# Controller.net
KiCad netlist of a schematic drawn in Altium Designer
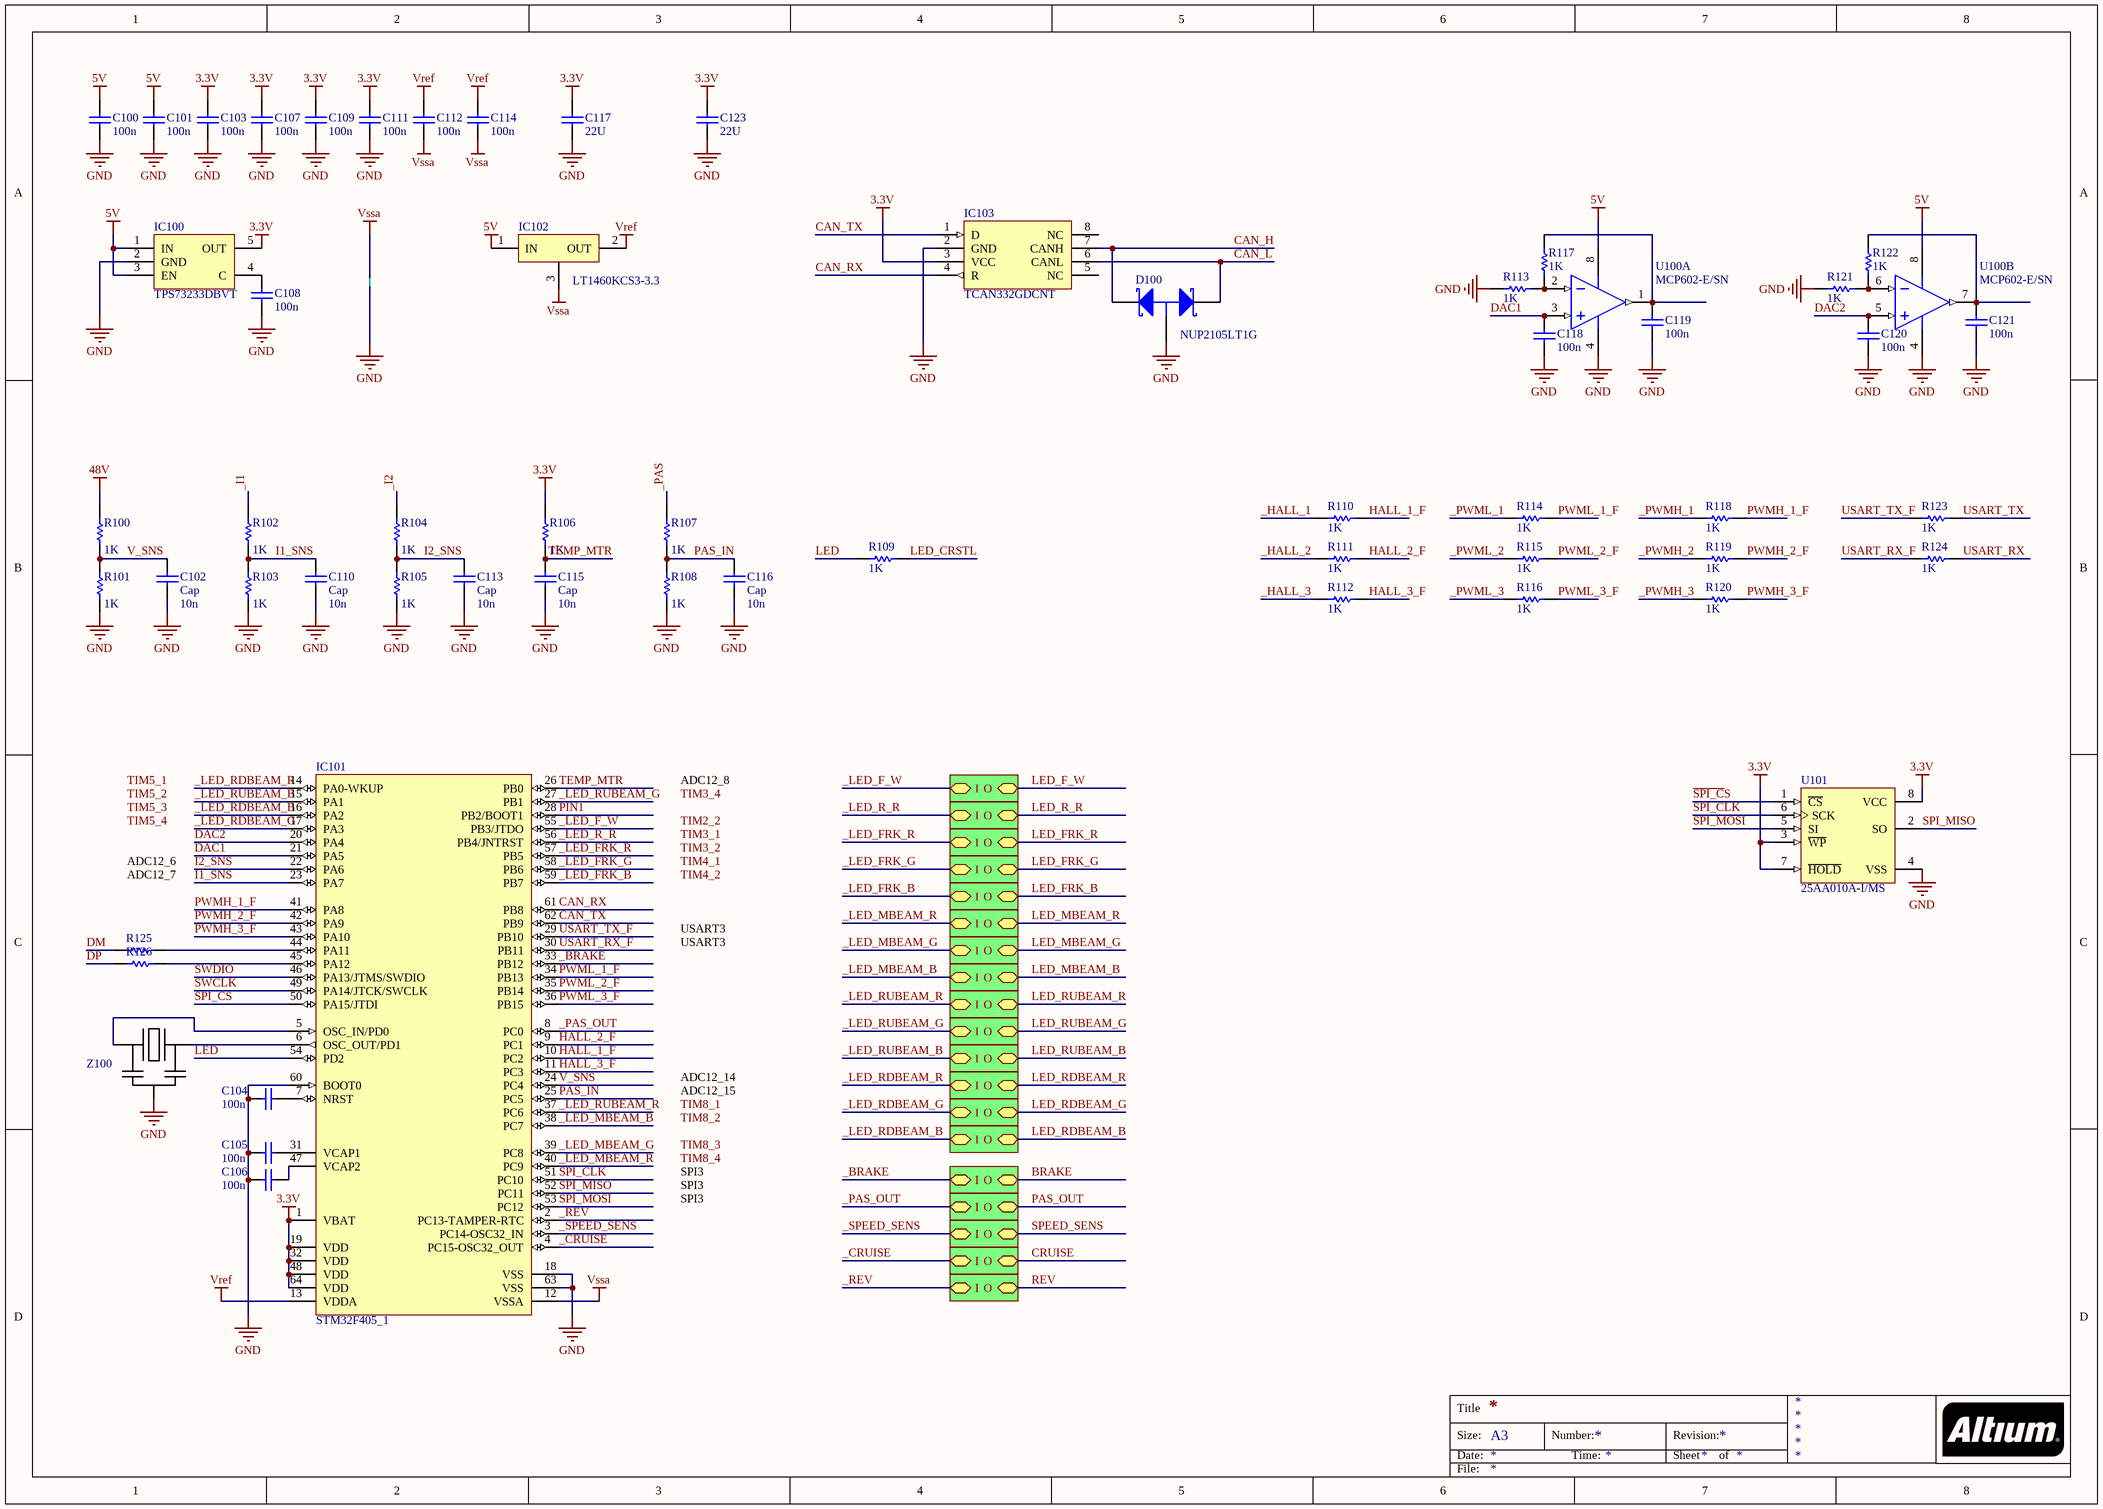
[diagram p0: Controller.SchDoc]

(export (version "E")
  (design (tool "Eeschema 10.0.6"))
  (components
    (comp (ref "C100")
      (value "100n")
      (footprint "0603x")
      (description "Capacitor")
      (fields (field (name "Comment") "Cap") (field (name "PUBLISHER") "Altium Limited"))
      (libsource (lib "Miscellaneous Devices") (part "Cap"))
    )
    (comp (ref "C101")
      (value "100n")
      (footprint "0603x")
      (description "Capacitor")
      (fields (field (name "Comment") "Cap") (field (name "PUBLISHER") "Altium Limited"))
      (libsource (lib "Miscellaneous Devices") (part "Cap"))
    )
    (comp (ref "C102")
      (value "Cap")
      (footprint "0603x")
      (description "Capacitor")
      (fields (field (name "ALTIUM_VALUE") "10n") (field (name "PUBLISHER") "Altium Limited"))
      (libsource (lib "Miscellaneous Devices") (part "Cap"))
    )
    (comp (ref "C103")
      (value "100n")
      (footprint "0603x")
      (description "Capacitor")
      (fields (field (name "Comment") "Cap") (field (name "PUBLISHER") "Altium Limited"))
      (libsource (lib "Miscellaneous Devices") (part "Cap"))
    )
    (comp (ref "C104")
      (value "100n")
      (footprint "0402x")
      (description "Capacitor")
      (fields (field (name "Comment") "Cap") (field (name "PUBLISHER") "Altium Limited"))
      (libsource (lib "Miscellaneous Devices") (part "Cap"))
    )
    (comp (ref "C105")
      (value "100n")
      (footprint "0603x")
      (description "Capacitor")
      (fields (field (name "Comment") "Cap") (field (name "PUBLISHER") "Altium Limited"))
      (libsource (lib "Miscellaneous Devices") (part "Cap"))
    )
    (comp (ref "C106")
      (value "100n")
      (footprint "0603x")
      (description "Capacitor")
      (fields (field (name "Comment") "Cap") (field (name "PUBLISHER") "Altium Limited"))
      (libsource (lib "Miscellaneous Devices") (part "Cap"))
    )
    (comp (ref "C107")
      (value "100n")
      (footprint "0603x")
      (description "Capacitor")
      (fields (field (name "Comment") "Cap") (field (name "PUBLISHER") "Altium Limited"))
      (libsource (lib "Miscellaneous Devices") (part "Cap"))
    )
    (comp (ref "C108")
      (value "100n")
      (footprint "0603x")
      (description "Capacitor")
      (fields (field (name "Comment") "Cap") (field (name "PUBLISHER") "Altium Limited"))
      (libsource (lib "Miscellaneous Devices") (part "Cap"))
    )
    (comp (ref "C109")
      (value "100n")
      (footprint "0603x")
      (description "Capacitor")
      (fields (field (name "Comment") "Cap") (field (name "PUBLISHER") "Altium Limited"))
      (libsource (lib "Miscellaneous Devices") (part "Cap"))
    )
    (comp (ref "C110")
      (value "Cap")
      (footprint "0603x")
      (description "Capacitor")
      (fields (field (name "ALTIUM_VALUE") "10n") (field (name "PUBLISHER") "Altium Limited"))
      (libsource (lib "Miscellaneous Devices") (part "Cap"))
    )
    (comp (ref "C111")
      (value "100n")
      (footprint "0603x")
      (description "Capacitor")
      (fields (field (name "Comment") "Cap") (field (name "PUBLISHER") "Altium Limited"))
      (libsource (lib "Miscellaneous Devices") (part "Cap"))
    )
    (comp (ref "C112")
      (value "100n")
      (footprint "0603x")
      (description "Capacitor")
      (fields (field (name "Comment") "Cap") (field (name "PUBLISHER") "Altium Limited"))
      (libsource (lib "Miscellaneous Devices") (part "Cap"))
    )
    (comp (ref "C113")
      (value "Cap")
      (footprint "0603x")
      (description "Capacitor")
      (fields (field (name "ALTIUM_VALUE") "10n") (field (name "PUBLISHER") "Altium Limited"))
      (libsource (lib "Miscellaneous Devices") (part "Cap"))
    )
    (comp (ref "C114")
      (value "100n")
      (footprint "0603x")
      (description "Capacitor")
      (fields (field (name "Comment") "Cap") (field (name "PUBLISHER") "Altium Limited"))
      (libsource (lib "Miscellaneous Devices") (part "Cap"))
    )
    (comp (ref "C115")
      (value "Cap")
      (footprint "0402x")
      (description "Capacitor")
      (fields (field (name "ALTIUM_VALUE") "10n") (field (name "PUBLISHER") "Altium Limited"))
      (libsource (lib "Miscellaneous Devices") (part "Cap"))
    )
    (comp (ref "C116")
      (value "Cap")
      (footprint "0603x")
      (description "Capacitor")
      (fields (field (name "ALTIUM_VALUE") "10n") (field (name "PUBLISHER") "Altium Limited"))
      (libsource (lib "Miscellaneous Devices") (part "Cap"))
    )
    (comp (ref "C117")
      (value "22U")
      (footprint "RR_B")
      (description "Capacitor")
      (fields (field (name "Comment") "Cap") (field (name "PUBLISHER") "Altium Limited"))
      (libsource (lib "Miscellaneous Devices") (part "Cap"))
    )
    (comp (ref "C118")
      (value "100n")
      (footprint "0603x")
      (description "Capacitor")
      (fields (field (name "Comment") "Cap") (field (name "PUBLISHER") "Altium Limited"))
      (libsource (lib "Miscellaneous Devices") (part "Cap"))
    )
    (comp (ref "C119")
      (value "100n")
      (footprint "0603x")
      (description "Capacitor")
      (fields (field (name "Comment") "Cap") (field (name "PUBLISHER") "Altium Limited"))
      (libsource (lib "Miscellaneous Devices") (part "Cap"))
    )
    (comp (ref "C120")
      (value "100n")
      (footprint "0603x")
      (description "Capacitor")
      (fields (field (name "Comment") "Cap") (field (name "PUBLISHER") "Altium Limited"))
      (libsource (lib "Miscellaneous Devices") (part "Cap"))
    )
    (comp (ref "C121")
      (value "100n")
      (footprint "0603x")
      (description "Capacitor")
      (fields (field (name "Comment") "Cap") (field (name "PUBLISHER") "Altium Limited"))
      (libsource (lib "Miscellaneous Devices") (part "Cap"))
    )
    (comp (ref "C123")
      (value "22U")
      (footprint "RR_B")
      (description "Capacitor")
      (fields (field (name "Comment") "Cap") (field (name "PUBLISHER") "Altium Limited"))
      (libsource (lib "Miscellaneous Devices") (part "Cap"))
    )
    (comp (ref "D100")
      (value "NUP2105LT1G")
      (footprint "SOT23_M")
      (description "Schottky Barrier Double Diode")
      (libsource (lib "EDDLib") (part "BAT54A"))
    )
    (comp (ref "IC100")
      (value "TPS73233DBVT")
      (footprint "SOT23-5_L")
      (libsource (lib "EDDLib") (part "TPS7xx33"))
    )
    (comp (ref "IC101")
      (value "STM32F405_1")
      (footprint "LQFP64_L")
      (description "STM32 ARM-based 32-bit MCU")
      (libsource (lib "EDDLib") (part "STM32F405_1"))
    )
    (comp (ref "IC102")
      (value "LT1460KCS3-3.3")
      (footprint "SOT-23")
      (libsource (lib "EDDLib") (part "PreciseRef"))
    )
    (comp (ref "IC103")
      (value "TCAN332GDCNT")
      (footprint "SOT23-8_L")
      (libsource (lib "EDDLib") (part "TCAN332GDCNT"))
    )
    (comp (ref "NT100")
      (value "NET_TIE")
      (footprint "NET_TIE_20mil")
      (description "Net tie")
      (libsource (lib "CustomLib") (part "Net tie"))
    )
    (comp (ref "R100")
      (value "1K")
      (footprint "0603x")
      (description "Resistor")
      (fields (field (name "Comment") "Res1") (field (name "PUBLISHER") "Altium Limited"))
      (libsource (lib "Miscellaneous Devices") (part "Res1"))
    )
    (comp (ref "R101")
      (value "1K")
      (footprint "0603x")
      (description "Resistor")
      (fields (field (name "Comment") "Res1") (field (name "PUBLISHER") "Altium Limited"))
      (libsource (lib "Miscellaneous Devices") (part "Res1"))
    )
    (comp (ref "R102")
      (value "1K")
      (footprint "0603x")
      (description "Resistor")
      (fields (field (name "Comment") "Res1") (field (name "PUBLISHER") "Altium Limited"))
      (libsource (lib "Miscellaneous Devices") (part "Res1"))
    )
    (comp (ref "R103")
      (value "1K")
      (footprint "0603x")
      (description "Resistor")
      (fields (field (name "Comment") "Res1") (field (name "PUBLISHER") "Altium Limited"))
      (libsource (lib "Miscellaneous Devices") (part "Res1"))
    )
    (comp (ref "R104")
      (value "1K")
      (footprint "0603x")
      (description "Resistor")
      (fields (field (name "Comment") "Res1") (field (name "PUBLISHER") "Altium Limited"))
      (libsource (lib "Miscellaneous Devices") (part "Res1"))
    )
    (comp (ref "R105")
      (value "1K")
      (footprint "0603x")
      (description "Resistor")
      (fields (field (name "Comment") "Res1") (field (name "PUBLISHER") "Altium Limited"))
      (libsource (lib "Miscellaneous Devices") (part "Res1"))
    )
    (comp (ref "R106")
      (value "1K")
      (footprint "0603x")
      (description "Resistor")
      (fields (field (name "Comment") "Res1") (field (name "PUBLISHER") "Altium Limited"))
      (libsource (lib "Miscellaneous Devices") (part "Res1"))
    )
    (comp (ref "R107")
      (value "1K")
      (footprint "0603x")
      (description "Resistor")
      (fields (field (name "Comment") "Res1") (field (name "PUBLISHER") "Altium Limited"))
      (libsource (lib "Miscellaneous Devices") (part "Res1"))
    )
    (comp (ref "R108")
      (value "1K")
      (footprint "0603x")
      (description "Resistor")
      (fields (field (name "Comment") "Res1") (field (name "PUBLISHER") "Altium Limited"))
      (libsource (lib "Miscellaneous Devices") (part "Res1"))
    )
    (comp (ref "R109")
      (value "1K")
      (footprint "0603x")
      (description "Resistor")
      (fields (field (name "Comment") "Res1") (field (name "PUBLISHER") "Altium Limited"))
      (libsource (lib "Miscellaneous Devices") (part "Res1"))
    )
    (comp (ref "R110")
      (value "1K")
      (footprint "0603x")
      (description "Resistor")
      (fields (field (name "Comment") "Res1") (field (name "PUBLISHER") "Altium Limited"))
      (libsource (lib "Miscellaneous Devices") (part "Res1"))
    )
    (comp (ref "R111")
      (value "1K")
      (footprint "0603x")
      (description "Resistor")
      (fields (field (name "Comment") "Res1") (field (name "PUBLISHER") "Altium Limited"))
      (libsource (lib "Miscellaneous Devices") (part "Res1"))
    )
    (comp (ref "R112")
      (value "1K")
      (footprint "0603x")
      (description "Resistor")
      (fields (field (name "Comment") "Res1") (field (name "PUBLISHER") "Altium Limited"))
      (libsource (lib "Miscellaneous Devices") (part "Res1"))
    )
    (comp (ref "R113")
      (value "1K")
      (footprint "0603x")
      (description "Resistor")
      (fields (field (name "Comment") "Res1") (field (name "PUBLISHER") "Altium Limited"))
      (libsource (lib "Miscellaneous Devices") (part "Res1"))
    )
    (comp (ref "R114")
      (value "1K")
      (footprint "0603x")
      (description "Resistor")
      (fields (field (name "Comment") "Res1") (field (name "PUBLISHER") "Altium Limited"))
      (libsource (lib "Miscellaneous Devices") (part "Res1"))
    )
    (comp (ref "R115")
      (value "1K")
      (footprint "0603x")
      (description "Resistor")
      (fields (field (name "Comment") "Res1") (field (name "PUBLISHER") "Altium Limited"))
      (libsource (lib "Miscellaneous Devices") (part "Res1"))
    )
    (comp (ref "R116")
      (value "1K")
      (footprint "0603x")
      (description "Resistor")
      (fields (field (name "Comment") "Res1") (field (name "PUBLISHER") "Altium Limited"))
      (libsource (lib "Miscellaneous Devices") (part "Res1"))
    )
    (comp (ref "R117")
      (value "1K")
      (footprint "0603x")
      (description "Resistor")
      (fields (field (name "Comment") "Res1") (field (name "PUBLISHER") "Altium Limited"))
      (libsource (lib "Miscellaneous Devices") (part "Res1"))
    )
    (comp (ref "R118")
      (value "1K")
      (footprint "0603x")
      (description "Resistor")
      (fields (field (name "Comment") "Res1") (field (name "PUBLISHER") "Altium Limited"))
      (libsource (lib "Miscellaneous Devices") (part "Res1"))
    )
    (comp (ref "R119")
      (value "1K")
      (footprint "0603x")
      (description "Resistor")
      (fields (field (name "Comment") "Res1") (field (name "PUBLISHER") "Altium Limited"))
      (libsource (lib "Miscellaneous Devices") (part "Res1"))
    )
    (comp (ref "R120")
      (value "1K")
      (footprint "0603x")
      (description "Resistor")
      (fields (field (name "Comment") "Res1") (field (name "PUBLISHER") "Altium Limited"))
      (libsource (lib "Miscellaneous Devices") (part "Res1"))
    )
    (comp (ref "R121")
      (value "1K")
      (footprint "0603x")
      (description "Resistor")
      (fields (field (name "Comment") "Res1") (field (name "PUBLISHER") "Altium Limited"))
      (libsource (lib "Miscellaneous Devices") (part "Res1"))
    )
    (comp (ref "R122")
      (value "1K")
      (footprint "0603x")
      (description "Resistor")
      (fields (field (name "Comment") "Res1") (field (name "PUBLISHER") "Altium Limited"))
      (libsource (lib "Miscellaneous Devices") (part "Res1"))
    )
    (comp (ref "R123")
      (value "1K")
      (footprint "0603x")
      (description "Resistor")
      (fields (field (name "Comment") "Res1") (field (name "PUBLISHER") "Altium Limited"))
      (libsource (lib "Miscellaneous Devices") (part "Res1"))
    )
    (comp (ref "R124")
      (value "1K")
      (footprint "0603x")
      (description "Resistor")
      (fields (field (name "Comment") "Res1") (field (name "PUBLISHER") "Altium Limited"))
      (libsource (lib "Miscellaneous Devices") (part "Res1"))
    )
    (comp (ref "R125")
      (value "Res1")
      (footprint "0603x")
      (description "Resistor")
      (fields (field (name "PUBLISHER") "Altium Limited"))
      (libsource (lib "Miscellaneous Devices") (part "Res1"))
    )
    (comp (ref "R126")
      (value "Res1")
      (footprint "0603x")
      (description "Resistor")
      (fields (field (name "PUBLISHER") "Altium Limited"))
      (libsource (lib "Miscellaneous Devices") (part "Res1"))
    )
    (comp (ref "U100")
      (value "MCP602-E/SN")
      (footprint "SOIC-SN8_N")
      (description "2.7V to 6.0V Single Supply CMOS Operational Amplifier, 8-Pin SOIC, Extended Temperature")
      (fields (field (name "PUBLISHER") "Altium Limited"))
      (libsource (lib "Microchip Linear Devices") (part "MCP602-E/SN"))
    )
    (comp (ref "U101")
      (value "25AA010A-I/MS")
      (footprint "SO-8_N")
      (description "1K SPI Bus Serial EEPROM, 8-Pin MSOP, Industrial Temperature")
      (fields (field (name "PUBLISHER") "Altium Limited"))
      (libsource (lib "Microchip Memory SPI Serial EEPROM") (part "25AA010A-I/MS"))
    )
    (comp (ref "Z100")
      (value "AWSCR-8.00CV-T")
      (footprint "CRYSTAL_3.2X1.3")
      (libsource (lib "EDDLib") (part "Crystal_smd_with_caps"))
    )
  )
  (nets
    (net (code "2") (name "/CAN_H") (class "Default")
      (node (ref "D100") (pin "2") (pinfunction "K2_2") (pintype "passive"))
      (node (ref "IC103") (pin "7") (pinfunction "CANH_7") (pintype "passive"))
    )
    (net (code "3") (name "/CAN_L") (class "Default")
      (node (ref "D100") (pin "3") (pinfunction "K1_3") (pintype "passive"))
      (node (ref "IC103") (pin "6") (pinfunction "CANL_6") (pintype "passive"))
    )
    (net (code "4") (name "/CAN_RX") (class "Default")
      (node (ref "IC101") (pin "61") (pinfunction "PB8_61") (pintype "bidirectional"))
      (node (ref "IC103") (pin "4") (pinfunction "R_4") (pintype "output"))
    )
    (net (code "5") (name "/CAN_TX") (class "Default")
      (node (ref "IC101") (pin "62") (pinfunction "PB9_62") (pintype "bidirectional"))
      (node (ref "IC103") (pin "1") (pinfunction "D_1") (pintype "input"))
    )
    (net (code "7") (name "/DAC1") (class "Default")
      (node (ref "C118") (pin "1") (pinfunction "1_1") (pintype "passive"))
      (node (ref "IC101") (pin "21") (pinfunction "PA5_21") (pintype "bidirectional"))
      (node (ref "U100") (pin "3") (pinfunction "VINA+_3") (pintype "input"))
    )
    (net (code "8") (name "/DAC2") (class "Default")
      (node (ref "C120") (pin "1") (pinfunction "1_1") (pintype "passive"))
      (node (ref "IC101") (pin "20") (pinfunction "PA4_20") (pintype "bidirectional"))
      (node (ref "U100") (pin "5") (pinfunction "VINB+_5") (pintype "input"))
    )
    (net (code "9") (name "/DM") (class "Default")
      (node (ref "R125") (pin "1") (pinfunction "1_1") (pintype "passive"))
    )
    (net (code "10") (name "/DP") (class "Default")
      (node (ref "R126") (pin "1") (pinfunction "1_1") (pintype "passive"))
    )
    (net (code "11") (name "/HALL_1_F") (class "Default")
      (node (ref "IC101") (pin "10") (pinfunction "PC2_10") (pintype "bidirectional"))
      (node (ref "R110") (pin "2") (pinfunction "2_2") (pintype "passive"))
    )
    (net (code "12") (name "/HALL_2_F") (class "Default")
      (node (ref "IC101") (pin "9") (pinfunction "PC1_9") (pintype "bidirectional"))
      (node (ref "R111") (pin "2") (pinfunction "2_2") (pintype "passive"))
    )
    (net (code "13") (name "/HALL_3_F") (class "Default")
      (node (ref "IC101") (pin "11") (pinfunction "PC3_11") (pintype "bidirectional"))
      (node (ref "R112") (pin "2") (pinfunction "2_2") (pintype "passive"))
    )
    (net (code "14") (name "/I1_SNS") (class "Default")
      (node (ref "C110") (pin "1") (pinfunction "1_1") (pintype "passive"))
      (node (ref "IC101") (pin "23") (pinfunction "PA7_23") (pintype "bidirectional"))
      (node (ref "R102") (pin "2") (pinfunction "2_2") (pintype "passive"))
      (node (ref "R103") (pin "1") (pinfunction "1_1") (pintype "passive"))
    )
    (net (code "15") (name "/I2_SNS") (class "Default")
      (node (ref "C113") (pin "1") (pinfunction "1_1") (pintype "passive"))
      (node (ref "IC101") (pin "22") (pinfunction "PA6_22") (pintype "bidirectional"))
      (node (ref "R104") (pin "2") (pinfunction "2_2") (pintype "passive"))
      (node (ref "R105") (pin "1") (pinfunction "1_1") (pintype "passive"))
    )
    (net (code "16") (name "/LED") (class "Default")
      (node (ref "IC101") (pin "54") (pinfunction "PD2_54") (pintype "bidirectional"))
      (node (ref "R109") (pin "1") (pinfunction "1_1") (pintype "passive"))
    )
    (net (code "17") (name "/LED_CRSTL") (class "Default")
      (node (ref "R109") (pin "2") (pinfunction "2_2") (pintype "passive"))
    )
    (net (code "32") (name "/PAS_IN") (class "Default")
      (node (ref "C116") (pin "1") (pinfunction "1_1") (pintype "passive"))
      (node (ref "IC101") (pin "25") (pinfunction "PC5_25") (pintype "bidirectional"))
      (node (ref "R107") (pin "2") (pinfunction "2_2") (pintype "passive"))
      (node (ref "R108") (pin "1") (pinfunction "1_1") (pintype "passive"))
    )
    (net (code "34") (name "/PIN1") (class "Default")
      (node (ref "IC101") (pin "28") (pinfunction "PB2/BOOT1_28") (pintype "bidirectional"))
    )
    (net (code "35") (name "/PWMH_1_F") (class "Default")
      (node (ref "IC101") (pin "41") (pinfunction "PA8_41") (pintype "bidirectional"))
      (node (ref "R118") (pin "2") (pinfunction "2_2") (pintype "passive"))
    )
    (net (code "36") (name "/PWMH_2_F") (class "Default")
      (node (ref "IC101") (pin "42") (pinfunction "PA9_42") (pintype "bidirectional"))
      (node (ref "R119") (pin "2") (pinfunction "2_2") (pintype "passive"))
    )
    (net (code "37") (name "/PWMH_3_F") (class "Default")
      (node (ref "IC101") (pin "43") (pinfunction "PA10_43") (pintype "bidirectional"))
      (node (ref "R120") (pin "2") (pinfunction "2_2") (pintype "passive"))
    )
    (net (code "38") (name "/PWML_1_F") (class "Default")
      (node (ref "IC101") (pin "34") (pinfunction "PB13_34") (pintype "bidirectional"))
      (node (ref "R114") (pin "2") (pinfunction "2_2") (pintype "passive"))
    )
    (net (code "39") (name "/PWML_2_F") (class "Default")
      (node (ref "IC101") (pin "35") (pinfunction "PB14_35") (pintype "bidirectional"))
      (node (ref "R115") (pin "2") (pinfunction "2_2") (pintype "passive"))
    )
    (net (code "40") (name "/PWML_3_F") (class "Default")
      (node (ref "IC101") (pin "36") (pinfunction "PB15_36") (pintype "bidirectional"))
      (node (ref "R116") (pin "2") (pinfunction "2_2") (pintype "passive"))
    )
    (net (code "43") (name "/SPI_CLK") (class "Default")
      (node (ref "IC101") (pin "51") (pinfunction "PC10_51") (pintype "bidirectional"))
      (node (ref "U101") (pin "6") (pinfunction "SCK_6") (pintype "input"))
    )
    (net (code "44") (name "/SPI_MISO") (class "Default")
      (node (ref "IC101") (pin "52") (pinfunction "PC11_52") (pintype "bidirectional"))
      (node (ref "U101") (pin "2") (pinfunction "SO_2") (pintype "tri_state"))
    )
    (net (code "45") (name "/SPI_MOSI") (class "Default")
      (node (ref "IC101") (pin "53") (pinfunction "PC12_53") (pintype "bidirectional"))
      (node (ref "U101") (pin "5") (pinfunction "SI_5") (pintype "input"))
    )
    (net (code "46") (name "/SWCLK") (class "Default")
      (node (ref "IC101") (pin "49") (pinfunction "PA14/JTCK/SWCLK_49") (pintype "bidirectional"))
    )
    (net (code "47") (name "/SWDIO") (class "Default")
      (node (ref "IC101") (pin "46") (pinfunction "PA13/JTMS/SWDIO_46") (pintype "bidirectional"))
    )
    (net (code "48") (name "/TEMP_MTR") (class "Default")
      (node (ref "C115") (pin "1") (pinfunction "1_1") (pintype "passive"))
      (node (ref "IC101") (pin "26") (pinfunction "PB0_26") (pintype "bidirectional"))
      (node (ref "R106") (pin "2") (pinfunction "2_2") (pintype "passive"))
    )
    (net (code "63") (name "/USART_RX") (class "Default")
      (node (ref "R124") (pin "2") (pinfunction "2_2") (pintype "passive"))
    )
    (net (code "64") (name "/USART_RX_F") (class "Default")
      (node (ref "IC101") (pin "30") (pinfunction "PB11_30") (pintype "bidirectional"))
      (node (ref "R124") (pin "1") (pinfunction "1_1") (pintype "passive"))
    )
    (net (code "65") (name "/USART_TX") (class "Default")
      (node (ref "R123") (pin "2") (pinfunction "2_2") (pintype "passive"))
    )
    (net (code "66") (name "/USART_TX_F") (class "Default")
      (node (ref "IC101") (pin "29") (pinfunction "PB10_29") (pintype "bidirectional"))
      (node (ref "R123") (pin "1") (pinfunction "1_1") (pintype "passive"))
    )
    (net (code "67") (name "/V_SNS") (class "Default")
      (node (ref "C102") (pin "1") (pinfunction "1_1") (pintype "passive"))
      (node (ref "IC101") (pin "24") (pinfunction "PC4_24") (pintype "bidirectional"))
      (node (ref "R100") (pin "2") (pinfunction "2_2") (pintype "passive"))
      (node (ref "R101") (pin "1") (pinfunction "1_1") (pintype "passive"))
    )
    (net (code "68") (name "/_BRAKE") (class "Default")
      (node (ref "IC101") (pin "33") (pinfunction "PB12_33") (pintype "bidirectional"))
    )
    (net (code "69") (name "/_CRUISE") (class "Default")
      (node (ref "IC101") (pin "4") (pinfunction "PC15-OSC32_OUT_4") (pintype "bidirectional"))
    )
    (net (code "70") (name "/_HALL_1") (class "Default")
      (node (ref "R110") (pin "1") (pinfunction "1_1") (pintype "passive"))
    )
    (net (code "71") (name "/_HALL_2") (class "Default")
      (node (ref "R111") (pin "1") (pinfunction "1_1") (pintype "passive"))
    )
    (net (code "72") (name "/_HALL_3") (class "Default")
      (node (ref "R112") (pin "1") (pinfunction "1_1") (pintype "passive"))
    )
    (net (code "73") (name "/_I1") (class "Default")
      (node (ref "R102") (pin "1") (pinfunction "1_1") (pintype "passive"))
    )
    (net (code "74") (name "/_I2") (class "Default")
      (node (ref "R104") (pin "1") (pinfunction "1_1") (pintype "passive"))
    )
    (net (code "75") (name "/_LED_FRK_B") (class "Default")
      (node (ref "IC101") (pin "59") (pinfunction "PB7_59") (pintype "bidirectional"))
    )
    (net (code "76") (name "/_LED_FRK_G") (class "Default")
      (node (ref "IC101") (pin "58") (pinfunction "PB6_58") (pintype "bidirectional"))
    )
    (net (code "77") (name "/_LED_FRK_R") (class "Default")
      (node (ref "IC101") (pin "57") (pinfunction "PB5_57") (pintype "bidirectional"))
    )
    (net (code "78") (name "/_LED_F_W") (class "Default")
      (node (ref "IC101") (pin "55") (pinfunction "PB3/JTDO_55") (pintype "bidirectional"))
    )
    (net (code "79") (name "/_LED_MBEAM_B") (class "Default")
      (node (ref "IC101") (pin "38") (pinfunction "PC7_38") (pintype "bidirectional"))
    )
    (net (code "80") (name "/_LED_MBEAM_G") (class "Default")
      (node (ref "IC101") (pin "39") (pinfunction "PC8_39") (pintype "bidirectional"))
    )
    (net (code "81") (name "/_LED_MBEAM_R") (class "Default")
      (node (ref "IC101") (pin "40") (pinfunction "PC9_40") (pintype "bidirectional"))
    )
    (net (code "82") (name "/_LED_RDBEAM_B") (class "Default")
      (node (ref "IC101") (pin "16") (pinfunction "PA2_16") (pintype "bidirectional"))
    )
    (net (code "83") (name "/_LED_RDBEAM_G") (class "Default")
      (node (ref "IC101") (pin "17") (pinfunction "PA3_17") (pintype "bidirectional"))
    )
    (net (code "84") (name "/_LED_RDBEAM_R") (class "Default")
      (node (ref "IC101") (pin "14") (pinfunction "PA0-WKUP_14") (pintype "bidirectional"))
    )
    (net (code "85") (name "/_LED_RUBEAM_B") (class "Default")
      (node (ref "IC101") (pin "15") (pinfunction "PA1_15") (pintype "bidirectional"))
    )
    (net (code "86") (name "/_LED_RUBEAM_G") (class "Default")
      (node (ref "IC101") (pin "27") (pinfunction "PB1_27") (pintype "bidirectional"))
    )
    (net (code "87") (name "/_LED_RUBEAM_R") (class "Default")
      (node (ref "IC101") (pin "37") (pinfunction "PC6_37") (pintype "bidirectional"))
    )
    (net (code "88") (name "/_LED_R_R") (class "Default")
      (node (ref "IC101") (pin "56") (pinfunction "PB4/JNTRST_56") (pintype "bidirectional"))
    )
    (net (code "89") (name "/_PAS") (class "Default")
      (node (ref "R107") (pin "1") (pinfunction "1_1") (pintype "passive"))
    )
    (net (code "90") (name "/_PAS_OUT") (class "Default")
      (node (ref "IC101") (pin "8") (pinfunction "PC0_8") (pintype "bidirectional"))
    )
    (net (code "91") (name "/_PWMH_1") (class "Default")
      (node (ref "R118") (pin "1") (pinfunction "1_1") (pintype "passive"))
    )
    (net (code "92") (name "/_PWMH_2") (class "Default")
      (node (ref "R119") (pin "1") (pinfunction "1_1") (pintype "passive"))
    )
    (net (code "93") (name "/_PWMH_3") (class "Default")
      (node (ref "R120") (pin "1") (pinfunction "1_1") (pintype "passive"))
    )
    (net (code "94") (name "/_PWML_1") (class "Default")
      (node (ref "R114") (pin "1") (pinfunction "1_1") (pintype "passive"))
    )
    (net (code "95") (name "/_PWML_2") (class "Default")
      (node (ref "R115") (pin "1") (pinfunction "1_1") (pintype "passive"))
    )
    (net (code "96") (name "/_PWML_3") (class "Default")
      (node (ref "R116") (pin "1") (pinfunction "1_1") (pintype "passive"))
    )
    (net (code "97") (name "/_REV") (class "Default")
      (node (ref "IC101") (pin "2") (pinfunction "PC13-TAMPER-RTC_2") (pintype "bidirectional"))
    )
    (net (code "98") (name "/_SPEED_SENS") (class "Default")
      (node (ref "IC101") (pin "3") (pinfunction "PC14-OSC32_IN_3") (pintype "bidirectional"))
    )
    (net (code "99") (name "/~{SPI_C}S") (class "Default")
      (node (ref "IC101") (pin "50") (pinfunction "PA15/JTDI_50") (pintype "bidirectional"))
      (node (ref "U101") (pin "1") (pinfunction "~{CS}_1") (pintype "input"))
    )
    (net (code "100") (name "3.3V") (class "Default")
      (node (ref "C103") (pin "1") (pinfunction "1_1") (pintype "passive"))
      (node (ref "C107") (pin "1") (pinfunction "1_1") (pintype "passive"))
      (node (ref "C109") (pin "1") (pinfunction "1_1") (pintype "passive"))
      (node (ref "C111") (pin "1") (pinfunction "1_1") (pintype "passive"))
      (node (ref "C117") (pin "1") (pinfunction "1_1") (pintype "passive"))
      (node (ref "C123") (pin "1") (pinfunction "1_1") (pintype "passive"))
      (node (ref "IC100") (pin "5") (pinfunction "OUT_5") (pintype "passive"))
      (node (ref "IC101") (pin "1") (pinfunction "VBAT_1") (pintype "power_in"))
      (node (ref "IC101") (pin "19") (pinfunction "VDD_19") (pintype "power_in"))
      (node (ref "IC101") (pin "32") (pinfunction "VDD_32") (pintype "power_in"))
      (node (ref "IC101") (pin "48") (pinfunction "VDD_48") (pintype "power_in"))
      (node (ref "IC101") (pin "64") (pinfunction "VDD_64") (pintype "power_in"))
      (node (ref "IC103") (pin "3") (pinfunction "VCC_3") (pintype "passive"))
      (node (ref "R106") (pin "1") (pinfunction "1_1") (pintype "passive"))
      (node (ref "U101") (pin "3") (pinfunction "~{WP}_3") (pintype "input"))
      (node (ref "U101") (pin "7") (pinfunction "~{HOLD}_7") (pintype "input"))
      (node (ref "U101") (pin "8") (pinfunction "VCC_8") (pintype "power_in"))
    )
    (net (code "101") (name "5V") (class "Default")
      (node (ref "C100") (pin "1") (pinfunction "1_1") (pintype "passive"))
      (node (ref "C101") (pin "1") (pinfunction "1_1") (pintype "passive"))
      (node (ref "IC100") (pin "1") (pinfunction "IN_1") (pintype "passive"))
      (node (ref "IC100") (pin "3") (pinfunction "EN_3") (pintype "passive"))
      (node (ref "IC102") (pin "1") (pinfunction "IN_1") (pintype "passive"))
      (node (ref "U100") (pin "8") (pinfunction "VDD_8") (pintype "power_in"))
    )
    (net (code "102") (name "48V") (class "Default")
      (node (ref "R100") (pin "1") (pinfunction "1_1") (pintype "passive"))
    )
    (net (code "103") (name "GND") (class "Default")
      (node (ref "C100") (pin "2") (pinfunction "2_2") (pintype "passive"))
      (node (ref "C101") (pin "2") (pinfunction "2_2") (pintype "passive"))
      (node (ref "C102") (pin "2") (pinfunction "2_2") (pintype "passive"))
      (node (ref "C103") (pin "2") (pinfunction "2_2") (pintype "passive"))
      (node (ref "C104") (pin "2") (pinfunction "2_2") (pintype "passive"))
      (node (ref "C105") (pin "2") (pinfunction "2_2") (pintype "passive"))
      (node (ref "C106") (pin "2") (pinfunction "2_2") (pintype "passive"))
      (node (ref "C107") (pin "2") (pinfunction "2_2") (pintype "passive"))
      (node (ref "C108") (pin "2") (pinfunction "2_2") (pintype "passive"))
      (node (ref "C109") (pin "2") (pinfunction "2_2") (pintype "passive"))
      (node (ref "C110") (pin "2") (pinfunction "2_2") (pintype "passive"))
      (node (ref "C111") (pin "2") (pinfunction "2_2") (pintype "passive"))
      (node (ref "C113") (pin "2") (pinfunction "2_2") (pintype "passive"))
      (node (ref "C115") (pin "2") (pinfunction "2_2") (pintype "passive"))
      (node (ref "C116") (pin "2") (pinfunction "2_2") (pintype "passive"))
      (node (ref "C117") (pin "2") (pinfunction "2_2") (pintype "passive"))
      (node (ref "C118") (pin "2") (pinfunction "2_2") (pintype "passive"))
      (node (ref "C119") (pin "2") (pinfunction "2_2") (pintype "passive"))
      (node (ref "C120") (pin "2") (pinfunction "2_2") (pintype "passive"))
      (node (ref "C121") (pin "2") (pinfunction "2_2") (pintype "passive"))
      (node (ref "C123") (pin "2") (pinfunction "2_2") (pintype "passive"))
      (node (ref "D100") (pin "1") (pinfunction "A_1") (pintype "passive"))
      (node (ref "IC100") (pin "2") (pinfunction "GND_2") (pintype "passive"))
      (node (ref "IC101") (pin "18") (pinfunction "VSS_18") (pintype "passive"))
      (node (ref "IC101") (pin "60") (pinfunction "BOOT0_60") (pintype "input"))
      (node (ref "IC101") (pin "63") (pinfunction "VSS_63") (pintype "power_in"))
      (node (ref "IC103") (pin "2") (pinfunction "GND_2") (pintype "power_in"))
      (node (ref "NT100") (pin "1") (pinfunction "1_1") (pintype "passive"))
      (node (ref "R101") (pin "2") (pinfunction "2_2") (pintype "passive"))
      (node (ref "R103") (pin "2") (pinfunction "2_2") (pintype "passive"))
      (node (ref "R105") (pin "2") (pinfunction "2_2") (pintype "passive"))
      (node (ref "R108") (pin "2") (pinfunction "2_2") (pintype "passive"))
      (node (ref "R113") (pin "1") (pinfunction "1_1") (pintype "passive"))
      (node (ref "R121") (pin "1") (pinfunction "1_1") (pintype "passive"))
      (node (ref "U100") (pin "4") (pinfunction "VSS_4") (pintype "power_in"))
      (node (ref "U101") (pin "4") (pinfunction "VSS_4") (pintype "power_in"))
      (node (ref "Z100") (pin "2") (pinfunction "GND_2") (pintype "passive"))
    )
    (net (code "104") (name "Net-(IC100-C)") (class "Default")
      (node (ref "C108") (pin "1") (pinfunction "1_1") (pintype "passive"))
      (node (ref "IC100") (pin "4") (pinfunction "C_4") (pintype "passive"))
    )
    (net (code "105") (name "Net-(IC101-NRST)") (class "Default")
      (node (ref "C104") (pin "1") (pinfunction "1_1") (pintype "passive"))
      (node (ref "IC101") (pin "7") (pinfunction "NRST_7") (pintype "bidirectional"))
    )
    (net (code "106") (name "Net-(IC101-OSC_IN{slash}PD0)") (class "Default")
      (node (ref "IC101") (pin "5") (pinfunction "OSC_IN/PD0_5") (pintype "input"))
      (node (ref "Z100") (pin "1") (pinfunction "X1_1") (pintype "passive"))
    )
    (net (code "107") (name "Net-(IC101-OSC_OUT{slash}PD1)") (class "Default")
      (node (ref "IC101") (pin "6") (pinfunction "OSC_OUT/PD1_6") (pintype "output"))
      (node (ref "Z100") (pin "3") (pinfunction "X2_3") (pintype "passive"))
    )
    (net (code "108") (name "Net-(IC101-PA11)") (class "Default")
      (node (ref "IC101") (pin "44") (pinfunction "PA11_44") (pintype "bidirectional"))
      (node (ref "R125") (pin "2") (pinfunction "2_2") (pintype "passive"))
    )
    (net (code "109") (name "Net-(IC101-PA12)") (class "Default")
      (node (ref "IC101") (pin "45") (pinfunction "PA12_45") (pintype "bidirectional"))
      (node (ref "R126") (pin "2") (pinfunction "2_2") (pintype "passive"))
    )
    (net (code "110") (name "Net-(IC101-VCAP1)") (class "Default")
      (node (ref "C105") (pin "1") (pinfunction "1_1") (pintype "passive"))
      (node (ref "IC101") (pin "31") (pinfunction "VCAP1_31") (pintype "power_in"))
    )
    (net (code "111") (name "Net-(IC101-VCAP2)") (class "Default")
      (node (ref "C106") (pin "1") (pinfunction "1_1") (pintype "passive"))
      (node (ref "IC101") (pin "47") (pinfunction "VCAP2_47") (pintype "power_in"))
    )
    (net (code "112") (name "Net-(U100A-VINA-)") (class "Default")
      (node (ref "R113") (pin "2") (pinfunction "2_2") (pintype "passive"))
      (node (ref "R117") (pin "1") (pinfunction "1_1") (pintype "passive"))
      (node (ref "U100") (pin "2") (pinfunction "VINA-_2") (pintype "input"))
    )
    (net (code "113") (name "Net-(U100A-VOUTA)") (class "Default")
      (node (ref "C119") (pin "1") (pinfunction "1_1") (pintype "passive"))
      (node (ref "R117") (pin "2") (pinfunction "2_2") (pintype "passive"))
      (node (ref "U100") (pin "1") (pinfunction "VOUTA_1") (pintype "output"))
    )
    (net (code "114") (name "Net-(U100B-VINB-)") (class "Default")
      (node (ref "R121") (pin "2") (pinfunction "2_2") (pintype "passive"))
      (node (ref "R122") (pin "1") (pinfunction "1_1") (pintype "passive"))
      (node (ref "U100") (pin "6") (pinfunction "VINB-_6") (pintype "input"))
    )
    (net (code "115") (name "Net-(U100B-VOUTB)") (class "Default")
      (node (ref "C121") (pin "1") (pinfunction "1_1") (pintype "passive"))
      (node (ref "R122") (pin "2") (pinfunction "2_2") (pintype "passive"))
      (node (ref "U100") (pin "7") (pinfunction "VOUTB_7") (pintype "output"))
    )
    (net (code "116") (name "Vref") (class "Default")
      (node (ref "C112") (pin "1") (pinfunction "1_1") (pintype "passive"))
      (node (ref "C114") (pin "1") (pinfunction "1_1") (pintype "passive"))
      (node (ref "IC101") (pin "13") (pinfunction "VDDA_13") (pintype "power_in"))
      (node (ref "IC102") (pin "2") (pinfunction "OUT_2") (pintype "passive"))
    )
    (net (code "117") (name "Vssa") (class "Default")
      (node (ref "C112") (pin "2") (pinfunction "2_2") (pintype "passive"))
      (node (ref "C114") (pin "2") (pinfunction "2_2") (pintype "passive"))
      (node (ref "IC101") (pin "12") (pinfunction "VSSA_12") (pintype "power_in"))
      (node (ref "IC102") (pin "3") (pinfunction "GND_3") (pintype "passive"))
      (node (ref "NT100") (pin "2") (pinfunction "2_2") (pintype "passive"))
    )
    (net (code "118") (name "unconnected-(IC103-NC-Pad5)") (class "Default")
      (node (ref "IC103") (pin "5") (pinfunction "NC_5") (pintype "passive"))
    )
    (net (code "119") (name "unconnected-(IC103-NC-Pad8)") (class "Default")
      (node (ref "IC103") (pin "8") (pinfunction "NC_8") (pintype "passive"))
    )
  )
)
